# Power.net
KiCad netlist of a schematic drawn in Altium Designer
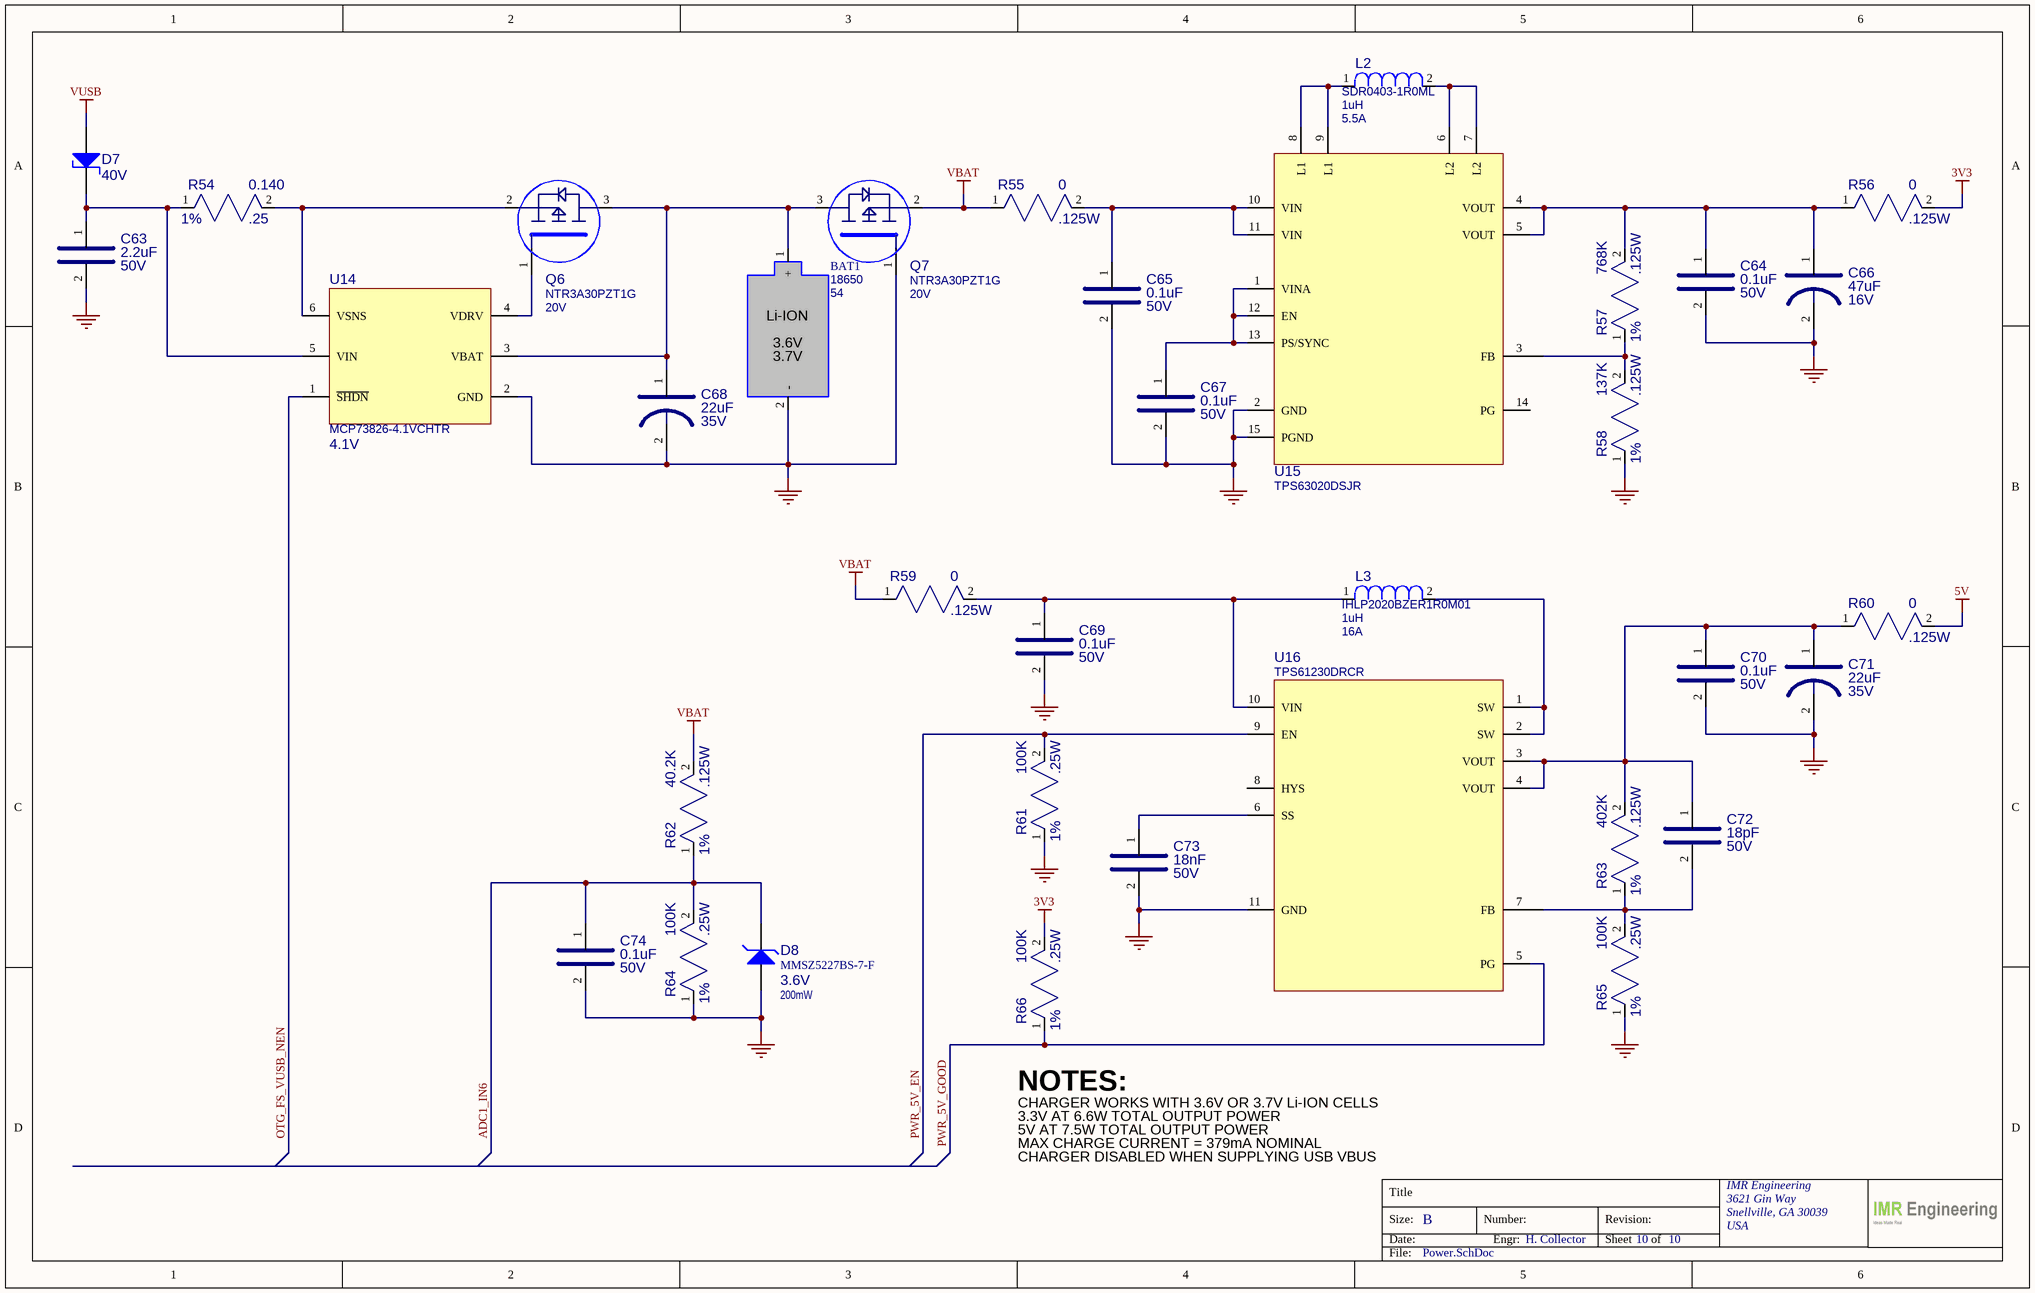
[diagram p0: Power.SchDoc]

(export (version "E")
  (design (tool "Eeschema 10.0.6"))
  (components
    (comp (ref "BAT1")
      (value "18650")
      (footprint "CONN_BATTERY_18650")
      (description "BATTERY CONTACT CLP 18650 PC PIN (NOTE: QTY x2)")
      (fields
        (field (name "MFG") "Keystone Electronics")
        (field (name "MFG_PN") "54")
        (field (name "Comment") "54")
      )
      (libsource (lib "IMR_Lib") (part "CONN_BATTERY_18650"))
    )
    (comp (ref "C63")
      (value "2.2uF")
      (footprint "CAP_0805")
      (description "CAP CER 2.2UF 50V X7R 0805")
      (fields
        (field (name "MFG") "Taiyo Yuden")
        (field (name "TOLERANCE") "20%")
        (field (name "VOLTAGE") "50V")
      )
      (libsource (lib "IMR_Lib") (part "CAP_2.2UF_50V_0805"))
    )
    (comp (ref "C64")
      (value "0.1uF")
      (footprint "CAP_0805")
      (description "CAP CER 0.1UF 50V X7R 0805")
      (fields (field (name "MFG") "AVX") (field (name "TOLERANCE") "10%") (field (name "VOLTAGE") "50V"))
      (libsource (lib "IMR_Lib") (part "CAP_0.1UF_50V_0805"))
    )
    (comp (ref "C65")
      (value "0.1uF")
      (footprint "CAP_0805")
      (description "CAP CER 0.1UF 50V X7R 0805")
      (fields (field (name "MFG") "AVX") (field (name "TOLERANCE") "10%") (field (name "VOLTAGE") "50V"))
      (libsource (lib "IMR_Lib") (part "CAP_0.1UF_50V_0805"))
    )
    (comp (ref "C66")
      (value "47uF")
      (footprint "CAP_ALE_SMD_6.6x6.6")
      (description "CAP ALUM 47UF 20% 16V SMD")
      (fields (field (name "MFG") "NICHICON") (field (name "TOLERANCE") "20%") (field (name "VOLTAGE") "16V"))
      (libsource (lib "IMR_Lib") (part "CAP_47UF_16V_ALE_NF"))
    )
    (comp (ref "C67")
      (value "0.1uF")
      (footprint "CAP_0805")
      (description "CAP CER 0.1UF 50V X7R 0805")
      (fields (field (name "MFG") "AVX") (field (name "TOLERANCE") "10%") (field (name "VOLTAGE") "50V"))
      (libsource (lib "IMR_Lib") (part "CAP_0.1UF_50V_0805"))
    )
    (comp (ref "C68")
      (value "22uF")
      (footprint "CAP_ALE_SMD_6.6x6.6")
      (description "CAP, AL E, 22UF, 35V, 20%, ROHS")
      (fields (field (name "MFG") "NICHICON") (field (name "TOLERANCE") "20%") (field (name "VOLTAGE") "35V"))
      (libsource (lib "IMR_Lib") (part "CAP_22UF_35V_ALE_NF"))
    )
    (comp (ref "C69")
      (value "0.1uF")
      (footprint "CAP_0805")
      (description "CAP CER 0.1UF 50V X7R 0805")
      (fields (field (name "MFG") "AVX") (field (name "TOLERANCE") "10%") (field (name "VOLTAGE") "50V"))
      (libsource (lib "IMR_Lib") (part "CAP_0.1UF_50V_0805"))
    )
    (comp (ref "C70")
      (value "0.1uF")
      (footprint "CAP_0805")
      (description "CAP CER 0.1UF 50V X7R 0805")
      (fields (field (name "MFG") "AVX") (field (name "TOLERANCE") "10%") (field (name "VOLTAGE") "50V"))
      (libsource (lib "IMR_Lib") (part "CAP_0.1UF_50V_0805"))
    )
    (comp (ref "C71")
      (value "22uF")
      (footprint "CAP_ALE_SMD_6.6x6.6")
      (description "CAP, AL E, 22UF, 35V, 20%, ROHS")
      (fields (field (name "MFG") "NICHICON") (field (name "TOLERANCE") "20%") (field (name "VOLTAGE") "35V"))
      (libsource (lib "IMR_Lib") (part "CAP_22UF_35V_ALE_NF"))
    )
    (comp (ref "C72")
      (value "18pF")
      (footprint "CAP_0805")
      (description "CAP CER 18PF 50V C0G/NP0 0805")
      (fields
        (field (name "MFG") "Stackpole Electronics Inc")
        (field (name "TOLERANCE") "5%")
        (field (name "VOLTAGE") "50V")
      )
      (libsource (lib "IMR_Lib") (part "CAP_18PF_50V_0805"))
    )
    (comp (ref "C73")
      (value "18nF")
      (footprint "CAP_0805")
      (description "CAP CER 0.018UF 50V X7R 0805")
      (fields (field (name "MFG") "Yageo") (field (name "TOLERANCE") "10%") (field (name "VOLTAGE") "50V"))
      (libsource (lib "IMR_Lib") (part "CAP_18NF_50V_0805"))
    )
    (comp (ref "C74")
      (value "0.1uF")
      (footprint "CAP_0805")
      (description "CAP CER 0.1UF 50V X7R 0805")
      (fields (field (name "MFG") "AVX") (field (name "TOLERANCE") "10%") (field (name "VOLTAGE") "50V"))
      (libsource (lib "IMR_Lib") (part "CAP_0.1UF_50V_0805"))
    )
    (comp (ref "D7")
      (value "40V")
      (footprint "SMB")
      (description "DIODE SCHOTTKY 40V 2A SMB")
      (fields (field (name "MFG") "ON SEMICONDUCTOR") (field (name "Comment") "MBRS2040LT3G"))
      (libsource (lib "IMR_Lib") (part "DIODE_SCHOTTKY_MBRS2040LT3G"))
    )
    (comp (ref "D8")
      (value "3.6V")
      (footprint "SOD323")
      (description "DIODE ZENER 3.6V 200MW SOD323")
      (fields
        (field (name "MFG") "Vishay Semiconductor")
        (field (name "MFG_PN") "MMSZ5227BS-7-F")
        (field (name "POWER") "200mW")
        (field (name "Comment") "MMSZ5227BS-7-F")
      )
      (libsource (lib "IMR_Lib") (part "DIODE_ZENER_MMSZ5227BS-7-F"))
    )
    (comp (ref "L2")
      (value "1uH")
      (footprint "IND_SDR0403")
      (description "FIXED IND 1UH 3.8A 33 MOHM SMD")
      (fields
        (field (name "MFG") "Bourns Inc.")
        (field (name "TOLERANCE") "20%")
        (field (name "MFG_PN") "SDR0403-1R0ML")
        (field (name "CURRENT") "5.5A")
      )
      (libsource (lib "IMR_Lib") (part "INDUCTOR_SDR0403-1R0ML"))
    )
    (comp (ref "L3")
      (value "1uH")
      (footprint "INDPM5552X200N")
      (description "FIXED IND 1UH 3.8A 33 MOHM SMD")
      (fields
        (field (name "MFG") "Bourns Inc.")
        (field (name "TOLERANCE") "20%")
        (field (name "MFG_PN") "IHLP2020BZER1R0M01")
        (field (name "CURRENT") "16A")
      )
      (libsource (lib "IMR_Lib") (part "INDUCTOR_IHLP2020BZER1R0M01"))
    )
    (comp (ref "Q6")
      (value "20V")
      (footprint "SOT-23")
      (description "MOSFET P-CH 20V 3A SOT23-3")
      (fields
        (field (name "MFG") "ON Semiconductor")
        (field (name "MFG_PN") "NTR3A30PZT1G")
        (field (name "Comment") "NTR3A30PZT1G")
      )
      (libsource (lib "IMR_Lib") (part "MOSFET_PCH_NTR3A30PZT1G"))
    )
    (comp (ref "Q7")
      (value "20V")
      (footprint "SOT-23")
      (description "MOSFET P-CH 20V 3A SOT23-3")
      (fields
        (field (name "MFG") "ON Semiconductor")
        (field (name "MFG_PN") "NTR3A30PZT1G")
        (field (name "Comment") "NTR3A30PZT1G")
      )
      (libsource (lib "") (part "MOSFET_PCH_NTR3A30PZT1G_1"))
    )
    (comp (ref "R54")
      (value "0.140")
      (footprint "1206")
      (description "RES 0.14 OHM 1% 1/4W 1206")
      (fields
        (field (name "MFG") "Yageo")
        (field (name "TOLERANCE") "1%")
        (field (name "POWER") ".25")
        (field (name "Comment") "RL1206FR-070R14L")
      )
      (libsource (lib "IMR_Lib") (part "RES_0.140_1206_1/4W_1%"))
    )
    (comp (ref "R55")
      (value "0")
      (footprint "PMG_RES_0805")
      (description "RES SMD 0 OHM JUMPER 1/8W 0805")
      (fields (field (name "MFG") "Yageo") (field (name "TOLERANCE") "JUMPER") (field (name "POWER") ".125W"))
      (libsource (lib "IMR_Lib") (part "RES_0_0805_1/8W"))
    )
    (comp (ref "R56")
      (value "0")
      (footprint "PMG_RES_0805")
      (description "RES SMD 0 OHM JUMPER 1/8W 0805")
      (fields (field (name "MFG") "Yageo") (field (name "TOLERANCE") "JUMPER") (field (name "POWER") ".125W"))
      (libsource (lib "IMR_Lib") (part "RES_0_0805_1/8W"))
    )
    (comp (ref "R57")
      (value "768K")
      (footprint "PMG_RES_0805")
      (description "RES SMD 768K OHM 1% 1/8W 0805")
      (fields
        (field (name "MFG") "Yageo")
        (field (name "TOLERANCE") "1%")
        (field (name "POWER") ".125W")
        (field (name "Comment") "RC0805FR-07768KL")
      )
      (libsource (lib "IMR_Lib") (part "RES_768K_0805_1/8W_1%"))
    )
    (comp (ref "R58")
      (value "137K")
      (footprint "PMG_RES_0805")
      (description "RES SMD 137K OHM 1% 1/8W 0805")
      (fields
        (field (name "MFG") "Yageo")
        (field (name "TOLERANCE") "1%")
        (field (name "POWER") ".125W")
        (field (name "Comment") "RC0805FR-07137KL")
      )
      (libsource (lib "IMR_Lib") (part "RES_137K_0805_1/8W_1%"))
    )
    (comp (ref "R59")
      (value "0")
      (footprint "PMG_RES_0805")
      (description "RES SMD 0 OHM JUMPER 1/8W 0805")
      (fields (field (name "MFG") "Yageo") (field (name "TOLERANCE") "JUMPER") (field (name "POWER") ".125W"))
      (libsource (lib "IMR_Lib") (part "RES_0_0805_1/8W"))
    )
    (comp (ref "R60")
      (value "0")
      (footprint "PMG_RES_0805")
      (description "RES SMD 0 OHM JUMPER 1/8W 0805")
      (fields (field (name "MFG") "Yageo") (field (name "TOLERANCE") "JUMPER") (field (name "POWER") ".125W"))
      (libsource (lib "IMR_Lib") (part "RES_0_0805_1/8W"))
    )
    (comp (ref "R61")
      (value "100K")
      (footprint "PMG_RES_0805")
      (description "RES SMD 100K OHM 1% 1/4W 0805")
      (fields
        (field (name "MFG") "KOA Speer Electronics, Inc.")
        (field (name "TOLERANCE") "1%")
        (field (name "POWER") ".25W")
        (field (name "Comment") "RK73H2ATTD1003F")
      )
      (libsource (lib "IMR_Lib") (part "RES_100K_0805_1/4W_1%"))
    )
    (comp (ref "R62")
      (value "40.2K")
      (footprint "RES_0805")
      (description "RES SMD 40.2K OHM 1% 1/8W 0805")
      (fields
        (field (name "MFG") "Yageo")
        (field (name "TOLERANCE") "1%")
        (field (name "POWER") ".125W")
        (field (name "Comment") "RC0805FR-0740K2L")
      )
      (libsource (lib "IMR_Lib") (part "RES_40.2K_0805_1/8W_1%_1"))
    )
    (comp (ref "R63")
      (value "402K")
      (footprint "RES_0805")
      (description "RES SMD 402K OHM 1% 1/8W 0805")
      (fields
        (field (name "MFG") "Yageo")
        (field (name "TOLERANCE") "1%")
        (field (name "POWER") ".125W")
        (field (name "Comment") "RC0805FR-07402KL")
      )
      (libsource (lib "IMR_Lib") (part "RES_402K_0805_1/8W_1%"))
    )
    (comp (ref "R64")
      (value "100K")
      (footprint "PMG_RES_0805")
      (description "RES SMD 100K OHM 1% 1/4W 0805")
      (fields
        (field (name "MFG") "KOA Speer Electronics, Inc.")
        (field (name "TOLERANCE") "1%")
        (field (name "POWER") ".25W")
        (field (name "Comment") "RK73H2ATTD1003F")
      )
      (libsource (lib "IMR_Lib") (part "RES_100K_0805_1/4W_1%"))
    )
    (comp (ref "R65")
      (value "100K")
      (footprint "PMG_RES_0805")
      (description "RES SMD 100K OHM 1% 1/4W 0805")
      (fields
        (field (name "MFG") "KOA Speer Electronics, Inc.")
        (field (name "TOLERANCE") "1%")
        (field (name "POWER") ".25W")
        (field (name "Comment") "RK73H2ATTD1003F")
      )
      (libsource (lib "IMR_Lib") (part "RES_100K_0805_1/4W_1%"))
    )
    (comp (ref "R66")
      (value "100K")
      (footprint "PMG_RES_0805")
      (description "RES SMD 100K OHM 1% 1/4W 0805")
      (fields
        (field (name "MFG") "KOA Speer Electronics, Inc.")
        (field (name "TOLERANCE") "1%")
        (field (name "POWER") ".25W")
        (field (name "Comment") "RK73H2ATTD1003F")
      )
      (libsource (lib "IMR_Lib") (part "RES_100K_0805_1/4W_1%"))
    )
    (comp (ref "U14")
      (value "4.1V")
      (footprint "SOT23-6")
      (description "IC CONTROLLR LI-ION 4.1V SOT23-6")
      (fields
        (field (name "MFG") "Microchip Technology")
        (field (name "MFG_PN") "MCP73826-4.1VCHTR")
        (field (name "Comment") "MCP73826-4.1VCHTR")
      )
      (libsource (lib "IMR_Lib") (part "IC_MCP73826-4.1VCHTR"))
    )
    (comp (ref "U15")
      (value "TPS63020DSJR")
      (footprint "14VSON")
      (description "IC REG BCK BST ADJ 3.5A 14VSON")
      (fields (field (name "MFG") "Texas Instruments") (field (name "MFG_PN") "TPS63020DSJR"))
      (libsource (lib "IMR_Lib") (part "IC_TPS63020DSJR"))
    )
    (comp (ref "U16")
      (value "TPS61230DRCR")
      (footprint "10VSON")
      (description "IC REG BOOST ADJ 4A 10VSON")
      (fields (field (name "MFG") "Texas Instruments") (field (name "MFG_PN") "TPS61230DRCR"))
      (libsource (lib "IMR_Lib") (part "IC_TPS61230DRCR"))
    )
  )
  (nets
    (net (code "1") (name "/ADC1_IN6") (class "Default")
      (node (ref "C74") (pin "1") (pinfunction "1_1") (pintype "passive"))
      (node (ref "D8") (pin "2") (pinfunction "K_2") (pintype "passive"))
      (node (ref "R62") (pin "1") (pinfunction "1_1") (pintype "passive"))
      (node (ref "R64") (pin "2") (pinfunction "2_2") (pintype "passive"))
    )
    (net (code "2") (name "/OTG_FS_VUSB_NEN") (class "Default")
      (node (ref "U14") (pin "1") (pinfunction "SHDN_1") (pintype "passive"))
    )
    (net (code "3") (name "/PWR_5V_EN") (class "Default")
      (node (ref "R61") (pin "2") (pinfunction "2_2") (pintype "passive"))
      (node (ref "U16") (pin "9") (pinfunction "EN_9") (pintype "passive"))
    )
    (net (code "4") (name "/PWR_5V_GOOD") (class "Default")
      (node (ref "R66") (pin "1") (pinfunction "1_1") (pintype "passive"))
      (node (ref "U16") (pin "5") (pinfunction "PG_5") (pintype "passive"))
    )
    (net (code "5") (name "3V3") (class "Default")
      (node (ref "R56") (pin "2") (pinfunction "2_2") (pintype "passive"))
      (node (ref "R66") (pin "2") (pinfunction "2_2") (pintype "passive"))
    )
    (net (code "6") (name "5V") (class "Default")
      (node (ref "R60") (pin "2") (pinfunction "2_2") (pintype "passive"))
    )
    (net (code "7") (name "GND") (class "Default")
      (node (ref "BAT1") (pin "2") (pinfunction "-_2") (pintype "passive"))
      (node (ref "C63") (pin "2") (pinfunction "2_2") (pintype "passive"))
      (node (ref "C64") (pin "2") (pinfunction "2_2") (pintype "passive"))
      (node (ref "C65") (pin "2") (pinfunction "2_2") (pintype "passive"))
      (node (ref "C66") (pin "2") (pinfunction "2_2") (pintype "passive"))
      (node (ref "C67") (pin "2") (pinfunction "2_2") (pintype "passive"))
      (node (ref "C68") (pin "2") (pinfunction "2_2") (pintype "passive"))
      (node (ref "C69") (pin "2") (pinfunction "2_2") (pintype "passive"))
      (node (ref "C70") (pin "2") (pinfunction "2_2") (pintype "passive"))
      (node (ref "C71") (pin "2") (pinfunction "2_2") (pintype "passive"))
      (node (ref "C73") (pin "2") (pinfunction "2_2") (pintype "passive"))
      (node (ref "C74") (pin "2") (pinfunction "2_2") (pintype "passive"))
      (node (ref "D8") (pin "1") (pinfunction "A_1") (pintype "passive"))
      (node (ref "Q7") (pin "1") (pinfunction "B_1") (pintype "passive"))
      (node (ref "R58") (pin "1") (pinfunction "1_1") (pintype "passive"))
      (node (ref "R61") (pin "1") (pinfunction "1_1") (pintype "passive"))
      (node (ref "R64") (pin "1") (pinfunction "1_1") (pintype "passive"))
      (node (ref "R65") (pin "1") (pinfunction "1_1") (pintype "passive"))
      (node (ref "U14") (pin "2") (pinfunction "GND_2") (pintype "passive"))
      (node (ref "U15") (pin "15") (pinfunction "PGND_15") (pintype "passive"))
      (node (ref "U15") (pin "2") (pinfunction "GND_2") (pintype "passive"))
      (node (ref "U16") (pin "11") (pinfunction "GND_11") (pintype "passive"))
    )
    (net (code "8") (name "Net-(BAT1-+)") (class "Default")
      (node (ref "BAT1") (pin "1") (pinfunction "+_1") (pintype "passive"))
      (node (ref "C68") (pin "1") (pinfunction "1_1") (pintype "passive"))
      (node (ref "Q6") (pin "3") (pinfunction "C_3") (pintype "passive"))
      (node (ref "Q7") (pin "3") (pinfunction "C_3") (pintype "passive"))
      (node (ref "U14") (pin "3") (pinfunction "VBAT_3") (pintype "passive"))
    )
    (net (code "9") (name "Net-(C64-Pad1)") (class "Default")
      (node (ref "C64") (pin "1") (pinfunction "1_1") (pintype "passive"))
      (node (ref "C66") (pin "1") (pinfunction "1_1") (pintype "passive"))
      (node (ref "R56") (pin "1") (pinfunction "1_1") (pintype "passive"))
      (node (ref "R57") (pin "2") (pinfunction "2_2") (pintype "passive"))
      (node (ref "U15") (pin "4") (pinfunction "VOUT_4") (pintype "passive"))
      (node (ref "U15") (pin "5") (pinfunction "VOUT_5") (pintype "passive"))
    )
    (net (code "10") (name "Net-(C65-Pad1)") (class "Default")
      (node (ref "C65") (pin "1") (pinfunction "1_1") (pintype "passive"))
      (node (ref "R55") (pin "2") (pinfunction "2_2") (pintype "passive"))
      (node (ref "U15") (pin "10") (pinfunction "VIN_10") (pintype "passive"))
      (node (ref "U15") (pin "11") (pinfunction "VIN_11") (pintype "passive"))
    )
    (net (code "11") (name "Net-(C70-Pad1)") (class "Default")
      (node (ref "C70") (pin "1") (pinfunction "1_1") (pintype "passive"))
      (node (ref "C71") (pin "1") (pinfunction "1_1") (pintype "passive"))
      (node (ref "C72") (pin "1") (pinfunction "1_1") (pintype "passive"))
      (node (ref "R60") (pin "1") (pinfunction "1_1") (pintype "passive"))
      (node (ref "R63") (pin "2") (pinfunction "2_2") (pintype "passive"))
      (node (ref "U16") (pin "3") (pinfunction "VOUT_3") (pintype "passive"))
      (node (ref "U16") (pin "4") (pinfunction "VOUT_4") (pintype "passive"))
    )
    (net (code "12") (name "Net-(D7-K)") (class "Default")
      (node (ref "C63") (pin "1") (pinfunction "1_1") (pintype "passive"))
      (node (ref "D7") (pin "2") (pinfunction "K_2") (pintype "passive"))
      (node (ref "R54") (pin "1") (pinfunction "1_1") (pintype "passive"))
      (node (ref "U14") (pin "5") (pinfunction "VIN_5") (pintype "passive"))
    )
    (net (code "13") (name "Net-(L2-Pad1)") (class "Default")
      (node (ref "L2") (pin "1") (pinfunction "1_1") (pintype "passive"))
      (node (ref "U15") (pin "8") (pinfunction "L1_8") (pintype "passive"))
      (node (ref "U15") (pin "9") (pinfunction "L1_9") (pintype "passive"))
    )
    (net (code "14") (name "Net-(L2-Pad2)") (class "Default")
      (node (ref "L2") (pin "2") (pinfunction "2_2") (pintype "passive"))
      (node (ref "U15") (pin "6") (pinfunction "L2_6") (pintype "passive"))
      (node (ref "U15") (pin "7") (pinfunction "L2_7") (pintype "passive"))
    )
    (net (code "15") (name "Net-(L3-Pad2)") (class "Default")
      (node (ref "L3") (pin "2") (pinfunction "2_2") (pintype "passive"))
      (node (ref "U16") (pin "1") (pinfunction "SW_1") (pintype "passive"))
      (node (ref "U16") (pin "2") (pinfunction "SW_2") (pintype "passive"))
    )
    (net (code "16") (name "Net-(Q6-B)") (class "Default")
      (node (ref "Q6") (pin "1") (pinfunction "B_1") (pintype "passive"))
      (node (ref "U14") (pin "4") (pinfunction "VDRV_4") (pintype "passive"))
    )
    (net (code "17") (name "Net-(Q6-E)") (class "Default")
      (node (ref "Q6") (pin "2") (pinfunction "E_2") (pintype "passive"))
      (node (ref "R54") (pin "2") (pinfunction "2_2") (pintype "passive"))
      (node (ref "U14") (pin "6") (pinfunction "VSNS_6") (pintype "passive"))
    )
    (net (code "18") (name "Net-(U15-EN)") (class "Default")
      (node (ref "C67") (pin "1") (pinfunction "1_1") (pintype "passive"))
      (node (ref "U15") (pin "1") (pinfunction "VINA_1") (pintype "passive"))
      (node (ref "U15") (pin "12") (pinfunction "EN_12") (pintype "passive"))
      (node (ref "U15") (pin "13") (pinfunction "PS/SYNC_13") (pintype "passive"))
    )
    (net (code "19") (name "Net-(U15-FB)") (class "Default")
      (node (ref "R57") (pin "1") (pinfunction "1_1") (pintype "passive"))
      (node (ref "R58") (pin "2") (pinfunction "2_2") (pintype "passive"))
      (node (ref "U15") (pin "3") (pinfunction "FB_3") (pintype "passive"))
    )
    (net (code "20") (name "Net-(U16-FB)") (class "Default")
      (node (ref "C72") (pin "2") (pinfunction "2_2") (pintype "passive"))
      (node (ref "R63") (pin "1") (pinfunction "1_1") (pintype "passive"))
      (node (ref "R65") (pin "2") (pinfunction "2_2") (pintype "passive"))
      (node (ref "U16") (pin "7") (pinfunction "FB_7") (pintype "passive"))
    )
    (net (code "21") (name "Net-(U16-SS)") (class "Default")
      (node (ref "C73") (pin "1") (pinfunction "1_1") (pintype "passive"))
      (node (ref "U16") (pin "6") (pinfunction "SS_6") (pintype "passive"))
    )
    (net (code "22") (name "Net-(U16-VIN)") (class "Default")
      (node (ref "C69") (pin "1") (pinfunction "1_1") (pintype "passive"))
      (node (ref "L3") (pin "1") (pinfunction "1_1") (pintype "passive"))
      (node (ref "R59") (pin "2") (pinfunction "2_2") (pintype "passive"))
      (node (ref "U16") (pin "10") (pinfunction "VIN_10") (pintype "passive"))
    )
    (net (code "23") (name "VBAT") (class "Default")
      (node (ref "Q7") (pin "2") (pinfunction "E_2") (pintype "passive"))
      (node (ref "R55") (pin "1") (pinfunction "1_1") (pintype "passive"))
      (node (ref "R59") (pin "1") (pinfunction "1_1") (pintype "passive"))
      (node (ref "R62") (pin "2") (pinfunction "2_2") (pintype "passive"))
    )
    (net (code "24") (name "VUSB") (class "Default")
      (node (ref "D7") (pin "1") (pinfunction "A_1") (pintype "passive"))
    )
    (net (code "25") (name "unconnected-(U15-PG-Pad14)") (class "Default")
      (node (ref "U15") (pin "14") (pinfunction "PG_14") (pintype "passive"))
    )
    (net (code "26") (name "unconnected-(U16-HYS-Pad8)") (class "Default")
      (node (ref "U16") (pin "8") (pinfunction "HYS_8") (pintype "passive"))
    )
  )
)
